# LTC2942-1.net
KiCad netlist of a schematic drawn in EAGLE
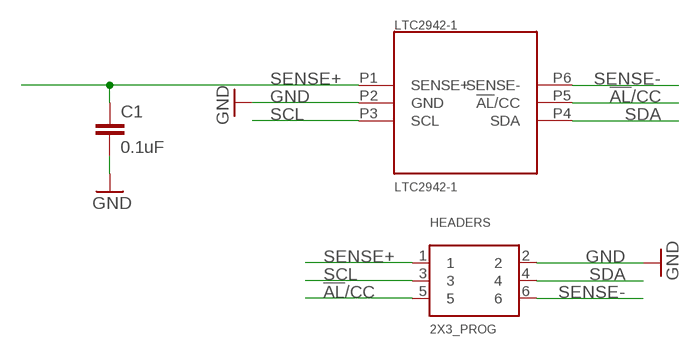
[diagram p0: schematic, sheet 1]

(export (version "E")
  (design (tool "Eeschema 10.0.6"))
  (components
    (comp (ref "C1")
      (value "0.1uF")
      (footprint "eagle-import:0805")
      (libsource (lib "eagle-import") (part "CAP"))
    )
    (comp (ref "HEADERS")
      (value "2X3_PROG")
      (footprint "eagle-import:2X3_0.1IN")
      (libsource (lib "eagle-import") (part "2X3_PROG"))
    )
    (comp (ref "LTC2942-1")
      (value "LTC2942-1")
      (footprint "eagle-import:LTC2942-1")
      (libsource (lib "eagle-import") (part "LTC2942-1"))
    )
  )
  (nets
    (net (code "1") (name "/SCL") (class "Default")
      (node (ref "HEADERS") (pin "3") (pinfunction "3_3") (pintype "bidirectional"))
      (node (ref "LTC2942-1") (pin "P3") (pinfunction "SCL_P3") (pintype "bidirectional"))
    )
    (net (code "2") (name "/SDA") (class "Default")
      (node (ref "HEADERS") (pin "4") (pinfunction "4_4") (pintype "bidirectional"))
      (node (ref "LTC2942-1") (pin "P4") (pinfunction "SDA_P4") (pintype "bidirectional"))
    )
    (net (code "3") (name "/SENSE+") (class "Default")
      (node (ref "C1") (pin "1") (pinfunction "1_1") (pintype "passive"))
      (node (ref "HEADERS") (pin "1") (pinfunction "1_1") (pintype "bidirectional"))
      (node (ref "LTC2942-1") (pin "P1") (pinfunction "SENSE+_P1") (pintype "bidirectional"))
    )
    (net (code "4") (name "/SENSE-") (class "Default")
      (node (ref "HEADERS") (pin "6") (pinfunction "6_6") (pintype "bidirectional"))
      (node (ref "LTC2942-1") (pin "P6") (pinfunction "SENSE-_P6") (pintype "bidirectional"))
    )
    (net (code "5") (name "/~{AL}{slash}CC") (class "Default")
      (node (ref "HEADERS") (pin "5") (pinfunction "5_5") (pintype "bidirectional"))
      (node (ref "LTC2942-1") (pin "P5") (pinfunction "~{AL}/CC_P5") (pintype "bidirectional"))
    )
    (net (code "6") (name "GND") (class "Default")
      (node (ref "C1") (pin "2") (pinfunction "2_2") (pintype "passive"))
      (node (ref "HEADERS") (pin "2") (pinfunction "2_2") (pintype "bidirectional"))
      (node (ref "LTC2942-1") (pin "P2") (pinfunction "GND_P2") (pintype "bidirectional"))
    )
  )
)
